# switch.net
KiCad netlist of a schematic drawn in EAGLE
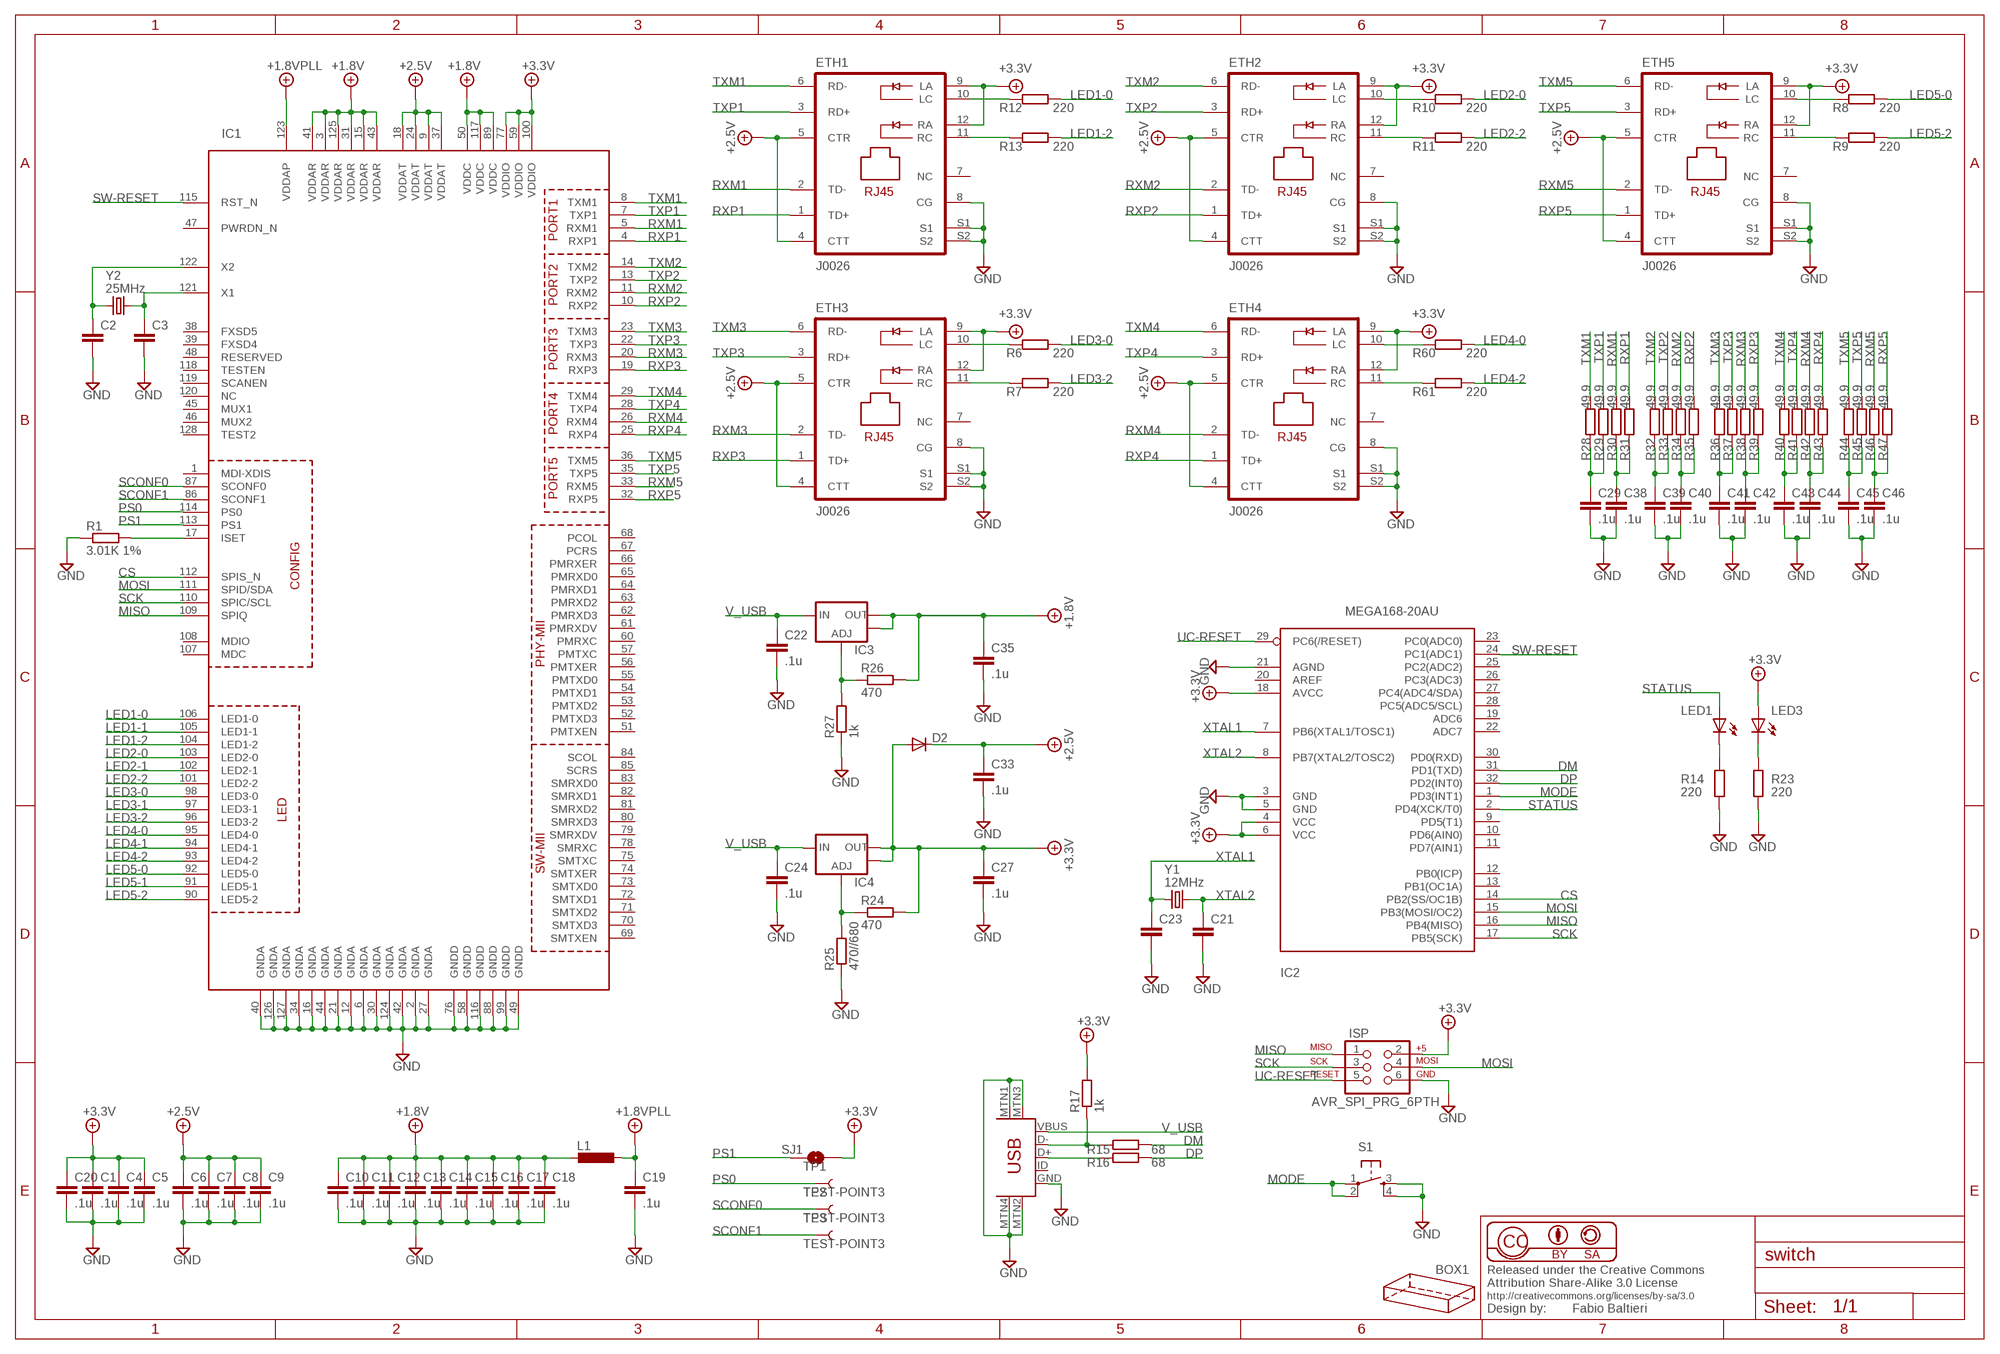
[diagram p0: schematic, sheet 1]

(export (version "E")
  (design (tool "Eeschema 10.0.6"))
  (components
    (comp (ref "BOX1")
      (value "HAMMOND-BOX-XXA")
      (footprint "eagle-import:1591XXA")
      (libsource (lib "eagle-import") (part "HAMMOND-BOX-XXA"))
    )
    (comp (ref "C1")
      (value ".1u")
      (footprint "eagle-import:C0805")
      (libsource (lib "eagle-import") (part "C-EUC0805"))
    )
    (comp (ref "C2")
      (value "C-EUC0805")
      (footprint "eagle-import:C0805")
      (libsource (lib "eagle-import") (part "C-EUC0805"))
    )
    (comp (ref "C3")
      (value "C-EUC0805")
      (footprint "eagle-import:C0805")
      (libsource (lib "eagle-import") (part "C-EUC0805"))
    )
    (comp (ref "C4")
      (value ".1u")
      (footprint "eagle-import:C0805")
      (libsource (lib "eagle-import") (part "C-EUC0805"))
    )
    (comp (ref "C5")
      (value ".1u")
      (footprint "eagle-import:C0805")
      (libsource (lib "eagle-import") (part "C-EUC0805"))
    )
    (comp (ref "C6")
      (value ".1u")
      (footprint "eagle-import:C0805")
      (libsource (lib "eagle-import") (part "C-EUC0805"))
    )
    (comp (ref "C7")
      (value ".1u")
      (footprint "eagle-import:C0805")
      (libsource (lib "eagle-import") (part "C-EUC0805"))
    )
    (comp (ref "C8")
      (value ".1u")
      (footprint "eagle-import:C0805")
      (libsource (lib "eagle-import") (part "C-EUC0805"))
    )
    (comp (ref "C9")
      (value ".1u")
      (footprint "eagle-import:C0805")
      (libsource (lib "eagle-import") (part "C-EUC0805"))
    )
    (comp (ref "C10")
      (value ".1u")
      (footprint "eagle-import:C0805")
      (libsource (lib "eagle-import") (part "C-EUC0805"))
    )
    (comp (ref "C11")
      (value ".1u")
      (footprint "eagle-import:C0805")
      (libsource (lib "eagle-import") (part "C-EUC0805"))
    )
    (comp (ref "C12")
      (value ".1u")
      (footprint "eagle-import:C0805")
      (libsource (lib "eagle-import") (part "C-EUC0805"))
    )
    (comp (ref "C13")
      (value ".1u")
      (footprint "eagle-import:C0805")
      (libsource (lib "eagle-import") (part "C-EUC0805"))
    )
    (comp (ref "C14")
      (value ".1u")
      (footprint "eagle-import:C0805")
      (libsource (lib "eagle-import") (part "C-EUC0805"))
    )
    (comp (ref "C15")
      (value ".1u")
      (footprint "eagle-import:C0805")
      (libsource (lib "eagle-import") (part "C-EUC0805"))
    )
    (comp (ref "C16")
      (value ".1u")
      (footprint "eagle-import:C0805")
      (libsource (lib "eagle-import") (part "C-EUC0805"))
    )
    (comp (ref "C17")
      (value ".1u")
      (footprint "eagle-import:C0805")
      (libsource (lib "eagle-import") (part "C-EUC0805"))
    )
    (comp (ref "C18")
      (value ".1u")
      (footprint "eagle-import:C0805")
      (libsource (lib "eagle-import") (part "C-EUC0805"))
    )
    (comp (ref "C19")
      (value ".1u")
      (footprint "eagle-import:C0805")
      (libsource (lib "eagle-import") (part "C-EUC0805"))
    )
    (comp (ref "C20")
      (value ".1u")
      (footprint "eagle-import:C0805")
      (libsource (lib "eagle-import") (part "C-EUC0805"))
    )
    (comp (ref "C21")
      (value "C-EUC0805")
      (footprint "eagle-import:C0805")
      (libsource (lib "eagle-import") (part "C-EUC0805"))
    )
    (comp (ref "C22")
      (value ".1u")
      (footprint "eagle-import:C0805")
      (libsource (lib "eagle-import") (part "C-EUC0805"))
    )
    (comp (ref "C23")
      (value "C-EUC0805")
      (footprint "eagle-import:C0805")
      (libsource (lib "eagle-import") (part "C-EUC0805"))
    )
    (comp (ref "C24")
      (value ".1u")
      (footprint "eagle-import:C0805")
      (libsource (lib "eagle-import") (part "C-EUC0805"))
    )
    (comp (ref "C27")
      (value ".1u")
      (footprint "eagle-import:C0805")
      (libsource (lib "eagle-import") (part "C-EUC0805"))
    )
    (comp (ref "C29")
      (value ".1u")
      (footprint "eagle-import:C0805")
      (libsource (lib "eagle-import") (part "C-EUC0805"))
    )
    (comp (ref "C33")
      (value ".1u")
      (footprint "eagle-import:C0805")
      (libsource (lib "eagle-import") (part "C-EUC0805"))
    )
    (comp (ref "C35")
      (value ".1u")
      (footprint "eagle-import:C0805")
      (libsource (lib "eagle-import") (part "C-EUC0805"))
    )
    (comp (ref "C38")
      (value ".1u")
      (footprint "eagle-import:C0805")
      (libsource (lib "eagle-import") (part "C-EUC0805"))
    )
    (comp (ref "C39")
      (value ".1u")
      (footprint "eagle-import:C0805")
      (libsource (lib "eagle-import") (part "C-EUC0805"))
    )
    (comp (ref "C40")
      (value ".1u")
      (footprint "eagle-import:C0805")
      (libsource (lib "eagle-import") (part "C-EUC0805"))
    )
    (comp (ref "C41")
      (value ".1u")
      (footprint "eagle-import:C0805")
      (libsource (lib "eagle-import") (part "C-EUC0805"))
    )
    (comp (ref "C42")
      (value ".1u")
      (footprint "eagle-import:C0805")
      (libsource (lib "eagle-import") (part "C-EUC0805"))
    )
    (comp (ref "C43")
      (value ".1u")
      (footprint "eagle-import:C0805")
      (libsource (lib "eagle-import") (part "C-EUC0805"))
    )
    (comp (ref "C44")
      (value ".1u")
      (footprint "eagle-import:C0805")
      (libsource (lib "eagle-import") (part "C-EUC0805"))
    )
    (comp (ref "C45")
      (value ".1u")
      (footprint "eagle-import:C0805")
      (libsource (lib "eagle-import") (part "C-EUC0805"))
    )
    (comp (ref "C46")
      (value ".1u")
      (footprint "eagle-import:C0805")
      (libsource (lib "eagle-import") (part "C-EUC0805"))
    )
    (comp (ref "D2")
      (value "DIODE-SMB")
      (footprint "eagle-import:SMB")
      (libsource (lib "eagle-import") (part "DIODE-SMB"))
    )
    (comp (ref "ETH1")
      (value "J0026")
      (footprint "eagle-import:PJ-J0")
      (libsource (lib "eagle-import") (part "J0026"))
    )
    (comp (ref "ETH2")
      (value "J0026")
      (footprint "eagle-import:PJ-J0")
      (libsource (lib "eagle-import") (part "J0026"))
    )
    (comp (ref "ETH3")
      (value "J0026")
      (footprint "eagle-import:PJ-J0")
      (libsource (lib "eagle-import") (part "J0026"))
    )
    (comp (ref "ETH4")
      (value "J0026")
      (footprint "eagle-import:PJ-J0")
      (libsource (lib "eagle-import") (part "J0026"))
    )
    (comp (ref "ETH5")
      (value "J0026")
      (footprint "eagle-import:PJ-J0")
      (libsource (lib "eagle-import") (part "J0026"))
    )
    (comp (ref "IC1")
      (value "KS8995MA")
      (footprint "eagle-import:PQFP128L")
      (libsource (lib "eagle-import") (part "KS8995MA"))
    )
    (comp (ref "IC2")
      (value "MEGA168-20AU")
      (footprint "eagle-import:MLF32")
      (libsource (lib "eagle-import") (part "MEGA8-MI"))
    )
    (comp (ref "IC3")
      (value "V_REG_LM1117SOT223")
      (footprint "eagle-import:SOT223")
      (libsource (lib "eagle-import") (part "V_REG_LM1117SOT223"))
    )
    (comp (ref "IC4")
      (value "V_REG_LM1117SOT223")
      (footprint "eagle-import:SOT223")
      (libsource (lib "eagle-import") (part "V_REG_LM1117SOT223"))
    )
    (comp (ref "ISP")
      (value "AVR_SPI_PRG_6PTH")
      (footprint "eagle-import:2X3")
      (libsource (lib "eagle-import") (part "AVR_SPI_PRG_6PTH"))
    )
    (comp (ref "L1")
      (value "L-EUL2012C")
      (footprint "eagle-import:L2012C")
      (libsource (lib "eagle-import") (part "L-EUL2012C"))
    )
    (comp (ref "LED1")
      (value "LEDCHIPLED_0603")
      (footprint "eagle-import:CHIPLED_0603")
      (libsource (lib "eagle-import") (part "LEDCHIPLED_0603"))
    )
    (comp (ref "LED3")
      (value "LEDCHIPLED_0603")
      (footprint "eagle-import:CHIPLED_0603")
      (libsource (lib "eagle-import") (part "LEDCHIPLED_0603"))
    )
    (comp (ref "R1")
      (value "3.01K 1%")
      (footprint "eagle-import:R0603")
      (libsource (lib "eagle-import") (part "R-EU_R0603"))
    )
    (comp (ref "R6")
      (value "220")
      (footprint "eagle-import:R0603")
      (libsource (lib "eagle-import") (part "R-EU_R0603"))
    )
    (comp (ref "R7")
      (value "220")
      (footprint "eagle-import:R0603")
      (libsource (lib "eagle-import") (part "R-EU_R0603"))
    )
    (comp (ref "R8")
      (value "220")
      (footprint "eagle-import:R0603")
      (libsource (lib "eagle-import") (part "R-EU_R0603"))
    )
    (comp (ref "R9")
      (value "220")
      (footprint "eagle-import:R0603")
      (libsource (lib "eagle-import") (part "R-EU_R0603"))
    )
    (comp (ref "R10")
      (value "220")
      (footprint "eagle-import:R0603")
      (libsource (lib "eagle-import") (part "R-EU_R0603"))
    )
    (comp (ref "R11")
      (value "220")
      (footprint "eagle-import:R0603")
      (libsource (lib "eagle-import") (part "R-EU_R0603"))
    )
    (comp (ref "R12")
      (value "220")
      (footprint "eagle-import:R0603")
      (libsource (lib "eagle-import") (part "R-EU_R0603"))
    )
    (comp (ref "R13")
      (value "220")
      (footprint "eagle-import:R0603")
      (libsource (lib "eagle-import") (part "R-EU_R0603"))
    )
    (comp (ref "R14")
      (value "220")
      (footprint "eagle-import:R0603")
      (libsource (lib "eagle-import") (part "R-EU_R0603"))
    )
    (comp (ref "R15")
      (value "68")
      (footprint "eagle-import:R0603")
      (libsource (lib "eagle-import") (part "R-EU_R0603"))
    )
    (comp (ref "R16")
      (value "68")
      (footprint "eagle-import:R0603")
      (libsource (lib "eagle-import") (part "R-EU_R0603"))
    )
    (comp (ref "R17")
      (value "1k")
      (footprint "eagle-import:R0603")
      (libsource (lib "eagle-import") (part "R-EU_R0603"))
    )
    (comp (ref "R23")
      (value "220")
      (footprint "eagle-import:R0603")
      (libsource (lib "eagle-import") (part "R-EU_R0603"))
    )
    (comp (ref "R24")
      (value "470")
      (footprint "eagle-import:R0603")
      (libsource (lib "eagle-import") (part "R-EU_R0603"))
    )
    (comp (ref "R25")
      (value "470//680")
      (footprint "eagle-import:R0603")
      (libsource (lib "eagle-import") (part "R-EU_R0603"))
    )
    (comp (ref "R26")
      (value "470")
      (footprint "eagle-import:R0603")
      (libsource (lib "eagle-import") (part "R-EU_R0603"))
    )
    (comp (ref "R27")
      (value "1k")
      (footprint "eagle-import:R0603")
      (libsource (lib "eagle-import") (part "R-EU_R0603"))
    )
    (comp (ref "R28")
      (value "49.9")
      (footprint "eagle-import:R0603")
      (libsource (lib "eagle-import") (part "R-EU_R0603"))
    )
    (comp (ref "R29")
      (value "49.9")
      (footprint "eagle-import:R0603")
      (libsource (lib "eagle-import") (part "R-EU_R0603"))
    )
    (comp (ref "R30")
      (value "49.9")
      (footprint "eagle-import:R0603")
      (libsource (lib "eagle-import") (part "R-EU_R0603"))
    )
    (comp (ref "R31")
      (value "49.9")
      (footprint "eagle-import:R0603")
      (libsource (lib "eagle-import") (part "R-EU_R0603"))
    )
    (comp (ref "R32")
      (value "49.9")
      (footprint "eagle-import:R0603")
      (libsource (lib "eagle-import") (part "R-EU_R0603"))
    )
    (comp (ref "R33")
      (value "49.9")
      (footprint "eagle-import:R0603")
      (libsource (lib "eagle-import") (part "R-EU_R0603"))
    )
    (comp (ref "R34")
      (value "49.9")
      (footprint "eagle-import:R0603")
      (libsource (lib "eagle-import") (part "R-EU_R0603"))
    )
    (comp (ref "R35")
      (value "49.9")
      (footprint "eagle-import:R0603")
      (libsource (lib "eagle-import") (part "R-EU_R0603"))
    )
    (comp (ref "R36")
      (value "49.9")
      (footprint "eagle-import:R0603")
      (libsource (lib "eagle-import") (part "R-EU_R0603"))
    )
    (comp (ref "R37")
      (value "49.9")
      (footprint "eagle-import:R0603")
      (libsource (lib "eagle-import") (part "R-EU_R0603"))
    )
    (comp (ref "R38")
      (value "49.9")
      (footprint "eagle-import:R0603")
      (libsource (lib "eagle-import") (part "R-EU_R0603"))
    )
    (comp (ref "R39")
      (value "49.9")
      (footprint "eagle-import:R0603")
      (libsource (lib "eagle-import") (part "R-EU_R0603"))
    )
    (comp (ref "R40")
      (value "49.9")
      (footprint "eagle-import:R0603")
      (libsource (lib "eagle-import") (part "R-EU_R0603"))
    )
    (comp (ref "R41")
      (value "49.9")
      (footprint "eagle-import:R0603")
      (libsource (lib "eagle-import") (part "R-EU_R0603"))
    )
    (comp (ref "R42")
      (value "49.9")
      (footprint "eagle-import:R0603")
      (libsource (lib "eagle-import") (part "R-EU_R0603"))
    )
    (comp (ref "R43")
      (value "49.9")
      (footprint "eagle-import:R0603")
      (libsource (lib "eagle-import") (part "R-EU_R0603"))
    )
    (comp (ref "R44")
      (value "49.9")
      (footprint "eagle-import:R0603")
      (libsource (lib "eagle-import") (part "R-EU_R0603"))
    )
    (comp (ref "R45")
      (value "49.9")
      (footprint "eagle-import:R0603")
      (libsource (lib "eagle-import") (part "R-EU_R0603"))
    )
    (comp (ref "R46")
      (value "49.9")
      (footprint "eagle-import:R0603")
      (libsource (lib "eagle-import") (part "R-EU_R0603"))
    )
    (comp (ref "R47")
      (value "49.9")
      (footprint "eagle-import:R0603")
      (libsource (lib "eagle-import") (part "R-EU_R0603"))
    )
    (comp (ref "R60")
      (value "220")
      (footprint "eagle-import:R0603")
      (libsource (lib "eagle-import") (part "R-EU_R0603"))
    )
    (comp (ref "R61")
      (value "220")
      (footprint "eagle-import:R0603")
      (libsource (lib "eagle-import") (part "R-EU_R0603"))
    )
    (comp (ref "S1")
      (value "TAC_SWITCHSMD")
      (footprint "eagle-import:TACTILE_SWITCH_SMD")
      (libsource (lib "eagle-import") (part "TAC_SWITCHSMD"))
    )
    (comp (ref "SJ1")
      (value "SOLDERJUMPERTRACE")
      (footprint "eagle-import:SJ_2S-TRACE")
      (libsource (lib "eagle-import") (part "SOLDERJUMPERTRACE"))
    )
    (comp (ref "TP1")
      (value "TEST-POINT3")
      (footprint "eagle-import:PAD.03X.03")
      (libsource (lib "eagle-import") (part "TEST-POINT3"))
    )
    (comp (ref "TP2")
      (value "TEST-POINT3")
      (footprint "eagle-import:PAD.03X.03")
      (libsource (lib "eagle-import") (part "TEST-POINT3"))
    )
    (comp (ref "TP3")
      (value "TEST-POINT3")
      (footprint "eagle-import:PAD.03X.03")
      (libsource (lib "eagle-import") (part "TEST-POINT3"))
    )
    (comp (ref "U$1")
      (value "USB-MINIB-5PIN")
      (footprint "eagle-import:USB-MINIB")
      (libsource (lib "eagle-import") (part "USB-MINIB-5PIN"))
    )
    (comp (ref "Y1")
      (value "12MHz")
      (footprint "eagle-import:CRYSTAL-SMD-5X3")
      (libsource (lib "eagle-import") (part "CRYSTAL5X3"))
    )
    (comp (ref "Y2")
      (value "25MHz")
      (footprint "eagle-import:CRYSTAL-SMD-5X3")
      (libsource (lib "eagle-import") (part "CRYSTAL5X3"))
    )
  )
  (nets
    (net (code "1") (name "+1.8V") (class "Default")
      (node (ref "C10") (pin "1") (pinfunction "1_1") (pintype "passive"))
      (node (ref "C11") (pin "1") (pinfunction "1_1") (pintype "passive"))
      (node (ref "C12") (pin "1") (pinfunction "1_1") (pintype "passive"))
      (node (ref "C13") (pin "1") (pinfunction "1_1") (pintype "passive"))
      (node (ref "C14") (pin "1") (pinfunction "1_1") (pintype "passive"))
      (node (ref "C15") (pin "1") (pinfunction "1_1") (pintype "passive"))
      (node (ref "C16") (pin "1") (pinfunction "1_1") (pintype "passive"))
      (node (ref "C17") (pin "1") (pinfunction "1_1") (pintype "passive"))
      (node (ref "C18") (pin "1") (pinfunction "1_1") (pintype "passive"))
      (node (ref "C35") (pin "1") (pinfunction "1_1") (pintype "passive"))
      (node (ref "IC1") (pin "117") (pinfunction "VDDC_117") (pintype "bidirectional"))
      (node (ref "IC1") (pin "125") (pinfunction "VDDAR_125") (pintype "bidirectional"))
      (node (ref "IC1") (pin "15") (pinfunction "VDDAR_15") (pintype "bidirectional"))
      (node (ref "IC1") (pin "3") (pinfunction "VDDAR_3") (pintype "bidirectional"))
      (node (ref "IC1") (pin "31") (pinfunction "VDDAR_31") (pintype "bidirectional"))
      (node (ref "IC1") (pin "41") (pinfunction "VDDAR_41") (pintype "bidirectional"))
      (node (ref "IC1") (pin "43") (pinfunction "VDDAR_43") (pintype "bidirectional"))
      (node (ref "IC1") (pin "50") (pinfunction "VDDC_50") (pintype "bidirectional"))
      (node (ref "IC1") (pin "89") (pinfunction "VDDC_89") (pintype "bidirectional"))
      (node (ref "IC3") (pin "2") (pinfunction "OUT_2") (pintype "output"))
      (node (ref "IC3") (pin "4") (pinfunction "OUT_4") (pintype "output"))
      (node (ref "L1") (pin "2") (pinfunction "2_2") (pintype "passive"))
      (node (ref "R26") (pin "2") (pinfunction "2_2") (pintype "passive"))
    )
    (net (code "2") (name "+1.8VPLL") (class "Default")
      (node (ref "C19") (pin "1") (pinfunction "1_1") (pintype "passive"))
      (node (ref "IC1") (pin "123") (pinfunction "VDDAP_123") (pintype "bidirectional"))
      (node (ref "L1") (pin "1") (pinfunction "1_1") (pintype "passive"))
    )
    (net (code "3") (name "+2.5V") (class "Default")
      (node (ref "C33") (pin "1") (pinfunction "1_1") (pintype "passive"))
      (node (ref "C6") (pin "1") (pinfunction "1_1") (pintype "passive"))
      (node (ref "C7") (pin "1") (pinfunction "1_1") (pintype "passive"))
      (node (ref "C8") (pin "1") (pinfunction "1_1") (pintype "passive"))
      (node (ref "C9") (pin "1") (pinfunction "1_1") (pintype "passive"))
      (node (ref "D2") (pin "C") (pinfunction "C_C") (pintype "passive"))
      (node (ref "ETH1") (pin "4") (pinfunction "CTT_4") (pintype "bidirectional"))
      (node (ref "ETH1") (pin "5") (pinfunction "CTR_5") (pintype "bidirectional"))
      (node (ref "ETH2") (pin "4") (pinfunction "CTT_4") (pintype "bidirectional"))
      (node (ref "ETH2") (pin "5") (pinfunction "CTR_5") (pintype "bidirectional"))
      (node (ref "ETH3") (pin "4") (pinfunction "CTT_4") (pintype "bidirectional"))
      (node (ref "ETH3") (pin "5") (pinfunction "CTR_5") (pintype "bidirectional"))
      (node (ref "ETH4") (pin "4") (pinfunction "CTT_4") (pintype "bidirectional"))
      (node (ref "ETH4") (pin "5") (pinfunction "CTR_5") (pintype "bidirectional"))
      (node (ref "ETH5") (pin "4") (pinfunction "CTT_4") (pintype "bidirectional"))
      (node (ref "ETH5") (pin "5") (pinfunction "CTR_5") (pintype "bidirectional"))
      (node (ref "IC1") (pin "18") (pinfunction "VDDAT_18") (pintype "bidirectional"))
      (node (ref "IC1") (pin "24") (pinfunction "VDDAT_24") (pintype "bidirectional"))
      (node (ref "IC1") (pin "37") (pinfunction "VDDAT_37") (pintype "bidirectional"))
      (node (ref "IC1") (pin "9") (pinfunction "VDDAT_9") (pintype "bidirectional"))
    )
    (net (code "4") (name "+3.3V") (class "Default")
      (node (ref "C1") (pin "1") (pinfunction "1_1") (pintype "passive"))
      (node (ref "C20") (pin "1") (pinfunction "1_1") (pintype "passive"))
      (node (ref "C27") (pin "1") (pinfunction "1_1") (pintype "passive"))
      (node (ref "C4") (pin "1") (pinfunction "1_1") (pintype "passive"))
      (node (ref "C5") (pin "1") (pinfunction "1_1") (pintype "passive"))
      (node (ref "D2") (pin "A") (pinfunction "A_A") (pintype "passive"))
      (node (ref "ETH1") (pin "12") (pinfunction "RA_12") (pintype "passive"))
      (node (ref "ETH1") (pin "9") (pinfunction "LA_9") (pintype "passive"))
      (node (ref "ETH2") (pin "12") (pinfunction "RA_12") (pintype "passive"))
      (node (ref "ETH2") (pin "9") (pinfunction "LA_9") (pintype "passive"))
      (node (ref "ETH3") (pin "12") (pinfunction "RA_12") (pintype "passive"))
      (node (ref "ETH3") (pin "9") (pinfunction "LA_9") (pintype "passive"))
      (node (ref "ETH4") (pin "12") (pinfunction "RA_12") (pintype "passive"))
      (node (ref "ETH4") (pin "9") (pinfunction "LA_9") (pintype "passive"))
      (node (ref "ETH5") (pin "12") (pinfunction "RA_12") (pintype "passive"))
      (node (ref "ETH5") (pin "9") (pinfunction "LA_9") (pintype "passive"))
      (node (ref "IC1") (pin "100") (pinfunction "VDDIO_100") (pintype "bidirectional"))
      (node (ref "IC1") (pin "59") (pinfunction "VDDIO_59") (pintype "bidirectional"))
      (node (ref "IC1") (pin "77") (pinfunction "VDDIO_77") (pintype "bidirectional"))
      (node (ref "IC2") (pin "18") (pinfunction "AVCC_18") (pintype "power_in"))
      (node (ref "IC2") (pin "4") (pinfunction "VCC_4") (pintype "power_in"))
      (node (ref "IC2") (pin "6") (pinfunction "VCC_6") (pintype "power_in"))
      (node (ref "IC4") (pin "2") (pinfunction "OUT_2") (pintype "output"))
      (node (ref "IC4") (pin "4") (pinfunction "OUT_4") (pintype "output"))
      (node (ref "ISP") (pin "2") (pinfunction "2_2") (pintype "passive"))
      (node (ref "LED3") (pin "A") (pinfunction "A_A") (pintype "passive"))
      (node (ref "R17") (pin "2") (pinfunction "2_2") (pintype "passive"))
      (node (ref "R24") (pin "2") (pinfunction "2_2") (pintype "passive"))
      (node (ref "SJ1") (pin "2") (pinfunction "2_2") (pintype "passive"))
    )
    (net (code "5") (name "/CS") (class "Default")
      (node (ref "IC1") (pin "112") (pinfunction "SPIS_N_112") (pintype "bidirectional"))
      (node (ref "IC2") (pin "14") (pinfunction "PB2(SS/OC1B)_14") (pintype "bidirectional"))
    )
    (net (code "6") (name "/DM") (class "Default")
      (node (ref "IC2") (pin "31") (pinfunction "PD1(TXD)_31") (pintype "bidirectional"))
      (node (ref "R15") (pin "1") (pinfunction "1_1") (pintype "passive"))
    )
    (net (code "7") (name "/DP") (class "Default")
      (node (ref "IC2") (pin "32") (pinfunction "PD2(INT0)_32") (pintype "bidirectional"))
      (node (ref "R16") (pin "1") (pinfunction "1_1") (pintype "passive"))
    )
    (net (code "8") (name "/LED1-0") (class "Default")
      (node (ref "IC1") (pin "106") (pinfunction "LED1-0_106") (pintype "bidirectional"))
      (node (ref "R12") (pin "1") (pinfunction "1_1") (pintype "passive"))
    )
    (net (code "9") (name "/LED1-1") (class "Default")
      (node (ref "IC1") (pin "105") (pinfunction "LED1-1_105") (pintype "bidirectional"))
    )
    (net (code "10") (name "/LED1-2") (class "Default")
      (node (ref "IC1") (pin "104") (pinfunction "LED1-2_104") (pintype "bidirectional"))
      (node (ref "R13") (pin "1") (pinfunction "1_1") (pintype "passive"))
    )
    (net (code "11") (name "/LED2-0") (class "Default")
      (node (ref "IC1") (pin "103") (pinfunction "LED2-0_103") (pintype "bidirectional"))
      (node (ref "R10") (pin "1") (pinfunction "1_1") (pintype "passive"))
    )
    (net (code "12") (name "/LED2-1") (class "Default")
      (node (ref "IC1") (pin "102") (pinfunction "LED2-1_102") (pintype "bidirectional"))
    )
    (net (code "13") (name "/LED2-2") (class "Default")
      (node (ref "IC1") (pin "101") (pinfunction "LED2-2_101") (pintype "bidirectional"))
      (node (ref "R11") (pin "1") (pinfunction "1_1") (pintype "passive"))
    )
    (net (code "14") (name "/LED3-0") (class "Default")
      (node (ref "IC1") (pin "98") (pinfunction "LED3-0_98") (pintype "bidirectional"))
      (node (ref "R6") (pin "1") (pinfunction "1_1") (pintype "passive"))
    )
    (net (code "15") (name "/LED3-1") (class "Default")
      (node (ref "IC1") (pin "97") (pinfunction "LED3-1_97") (pintype "bidirectional"))
    )
    (net (code "16") (name "/LED3-2") (class "Default")
      (node (ref "IC1") (pin "96") (pinfunction "LED3-2_96") (pintype "bidirectional"))
      (node (ref "R7") (pin "1") (pinfunction "1_1") (pintype "passive"))
    )
    (net (code "17") (name "/LED4-0") (class "Default")
      (node (ref "IC1") (pin "95") (pinfunction "LED4-0_95") (pintype "bidirectional"))
      (node (ref "R60") (pin "1") (pinfunction "1_1") (pintype "passive"))
    )
    (net (code "18") (name "/LED4-1") (class "Default")
      (node (ref "IC1") (pin "94") (pinfunction "LED4-1_94") (pintype "bidirectional"))
    )
    (net (code "19") (name "/LED4-2") (class "Default")
      (node (ref "IC1") (pin "93") (pinfunction "LED4-2_93") (pintype "bidirectional"))
      (node (ref "R61") (pin "1") (pinfunction "1_1") (pintype "passive"))
    )
    (net (code "20") (name "/LED5-0") (class "Default")
      (node (ref "IC1") (pin "92") (pinfunction "LED5-0_92") (pintype "bidirectional"))
      (node (ref "R8") (pin "1") (pinfunction "1_1") (pintype "passive"))
    )
    (net (code "21") (name "/LED5-1") (class "Default")
      (node (ref "IC1") (pin "91") (pinfunction "LED5-1_91") (pintype "bidirectional"))
    )
    (net (code "22") (name "/LED5-2") (class "Default")
      (node (ref "IC1") (pin "90") (pinfunction "LED5-2_90") (pintype "bidirectional"))
      (node (ref "R9") (pin "1") (pinfunction "1_1") (pintype "passive"))
    )
    (net (code "23") (name "/MISO") (class "Default")
      (node (ref "IC1") (pin "109") (pinfunction "SPIQ_109") (pintype "bidirectional"))
      (node (ref "IC2") (pin "16") (pinfunction "PB4(MISO)_16") (pintype "bidirectional"))
      (node (ref "ISP") (pin "1") (pinfunction "1_1") (pintype "passive"))
    )
    (net (code "24") (name "/MODE") (class "Default")
      (node (ref "IC2") (pin "1") (pinfunction "PD3(INT1)_1") (pintype "bidirectional"))
      (node (ref "S1") (pin "1") (pinfunction "1_1") (pintype "passive"))
      (node (ref "S1") (pin "2") (pinfunction "2_2") (pintype "passive"))
    )
    (net (code "25") (name "/MOSI") (class "Default")
      (node (ref "IC1") (pin "111") (pinfunction "SPID/SDA_111") (pintype "bidirectional"))
      (node (ref "IC2") (pin "15") (pinfunction "PB3(MOSI/OC2)_15") (pintype "bidirectional"))
      (node (ref "ISP") (pin "4") (pinfunction "4_4") (pintype "passive"))
    )
    (net (code "26") (name "/PS0") (class "Default")
      (node (ref "IC1") (pin "114") (pinfunction "PS0_114") (pintype "bidirectional"))
      (node (ref "TP1") (pin "P$1") (pinfunction "1_P$1") (pintype "bidirectional"))
    )
    (net (code "27") (name "/PS1") (class "Default")
      (node (ref "IC1") (pin "113") (pinfunction "PS1_113") (pintype "bidirectional"))
      (node (ref "SJ1") (pin "1") (pinfunction "1_1") (pintype "passive"))
    )
    (net (code "28") (name "/RXM1") (class "Default")
      (node (ref "ETH1") (pin "2") (pinfunction "TD-_2") (pintype "bidirectional"))
      (node (ref "IC1") (pin "5") (pinfunction "RXM1_5") (pintype "bidirectional"))
      (node (ref "R30") (pin "2") (pinfunction "2_2") (pintype "passive"))
    )
    (net (code "29") (name "/RXM2") (class "Default")
      (node (ref "ETH2") (pin "2") (pinfunction "TD-_2") (pintype "bidirectional"))
      (node (ref "IC1") (pin "11") (pinfunction "RXM2_11") (pintype "bidirectional"))
      (node (ref "R34") (pin "2") (pinfunction "2_2") (pintype "passive"))
    )
    (net (code "30") (name "/RXM3") (class "Default")
      (node (ref "ETH3") (pin "2") (pinfunction "TD-_2") (pintype "bidirectional"))
      (node (ref "IC1") (pin "20") (pinfunction "RXM3_20") (pintype "bidirectional"))
      (node (ref "R38") (pin "2") (pinfunction "2_2") (pintype "passive"))
    )
    (net (code "31") (name "/RXM4") (class "Default")
      (node (ref "ETH4") (pin "2") (pinfunction "TD-_2") (pintype "bidirectional"))
      (node (ref "IC1") (pin "26") (pinfunction "RXM4_26") (pintype "bidirectional"))
      (node (ref "R42") (pin "2") (pinfunction "2_2") (pintype "passive"))
    )
    (net (code "32") (name "/RXM5") (class "Default")
      (node (ref "ETH5") (pin "2") (pinfunction "TD-_2") (pintype "bidirectional"))
      (node (ref "IC1") (pin "33") (pinfunction "RXM5_33") (pintype "bidirectional"))
      (node (ref "R46") (pin "2") (pinfunction "2_2") (pintype "passive"))
    )
    (net (code "33") (name "/RXP1") (class "Default")
      (node (ref "ETH1") (pin "1") (pinfunction "TD+_1") (pintype "bidirectional"))
      (node (ref "IC1") (pin "4") (pinfunction "RXP1_4") (pintype "bidirectional"))
      (node (ref "R31") (pin "2") (pinfunction "2_2") (pintype "passive"))
    )
    (net (code "34") (name "/RXP2") (class "Default")
      (node (ref "ETH2") (pin "1") (pinfunction "TD+_1") (pintype "bidirectional"))
      (node (ref "IC1") (pin "10") (pinfunction "RXP2_10") (pintype "bidirectional"))
      (node (ref "R35") (pin "2") (pinfunction "2_2") (pintype "passive"))
    )
    (net (code "35") (name "/RXP3") (class "Default")
      (node (ref "ETH3") (pin "1") (pinfunction "TD+_1") (pintype "bidirectional"))
      (node (ref "IC1") (pin "19") (pinfunction "RXP3_19") (pintype "bidirectional"))
      (node (ref "R39") (pin "2") (pinfunction "2_2") (pintype "passive"))
    )
    (net (code "36") (name "/RXP4") (class "Default")
      (node (ref "ETH4") (pin "1") (pinfunction "TD+_1") (pintype "bidirectional"))
      (node (ref "IC1") (pin "25") (pinfunction "RXP4_25") (pintype "bidirectional"))
      (node (ref "R43") (pin "2") (pinfunction "2_2") (pintype "passive"))
    )
    (net (code "37") (name "/RXP5") (class "Default")
      (node (ref "ETH5") (pin "1") (pinfunction "TD+_1") (pintype "bidirectional"))
      (node (ref "IC1") (pin "32") (pinfunction "RXP5_32") (pintype "bidirectional"))
      (node (ref "R47") (pin "2") (pinfunction "2_2") (pintype "passive"))
    )
    (net (code "38") (name "/SCK") (class "Default")
      (node (ref "IC1") (pin "110") (pinfunction "SPIC/SCL_110") (pintype "bidirectional"))
      (node (ref "IC2") (pin "17") (pinfunction "PB5(SCK)_17") (pintype "bidirectional"))
      (node (ref "ISP") (pin "3") (pinfunction "3_3") (pintype "passive"))
    )
    (net (code "39") (name "/SCONF0") (class "Default")
      (node (ref "IC1") (pin "87") (pinfunction "SCONF0_87") (pintype "bidirectional"))
      (node (ref "TP2") (pin "P$1") (pinfunction "1_P$1") (pintype "bidirectional"))
    )
    (net (code "40") (name "/SCONF1") (class "Default")
      (node (ref "IC1") (pin "86") (pinfunction "SCONF1_86") (pintype "bidirectional"))
      (node (ref "TP3") (pin "P$1") (pinfunction "1_P$1") (pintype "bidirectional"))
    )
    (net (code "41") (name "/STATUS") (class "Default")
      (node (ref "IC2") (pin "2") (pinfunction "PD4(XCK/T0)_2") (pintype "bidirectional"))
      (node (ref "LED1") (pin "A") (pinfunction "A_A") (pintype "passive"))
    )
    (net (code "42") (name "/SW-RESET") (class "Default")
      (node (ref "IC1") (pin "115") (pinfunction "RST_N_115") (pintype "bidirectional"))
      (node (ref "IC2") (pin "24") (pinfunction "PC1(ADC1)_24") (pintype "bidirectional"))
    )
    (net (code "43") (name "/TXM1") (class "Default")
      (node (ref "ETH1") (pin "6") (pinfunction "RD-_6") (pintype "bidirectional"))
      (node (ref "IC1") (pin "8") (pinfunction "TXM1_8") (pintype "bidirectional"))
      (node (ref "R28") (pin "2") (pinfunction "2_2") (pintype "passive"))
    )
    (net (code "44") (name "/TXM2") (class "Default")
      (node (ref "ETH2") (pin "6") (pinfunction "RD-_6") (pintype "bidirectional"))
      (node (ref "IC1") (pin "14") (pinfunction "TXM2_14") (pintype "bidirectional"))
      (node (ref "R32") (pin "2") (pinfunction "2_2") (pintype "passive"))
    )
    (net (code "45") (name "/TXM3") (class "Default")
      (node (ref "ETH3") (pin "6") (pinfunction "RD-_6") (pintype "bidirectional"))
      (node (ref "IC1") (pin "23") (pinfunction "TXM3_23") (pintype "bidirectional"))
      (node (ref "R36") (pin "2") (pinfunction "2_2") (pintype "passive"))
    )
    (net (code "46") (name "/TXM4") (class "Default")
      (node (ref "ETH4") (pin "6") (pinfunction "RD-_6") (pintype "bidirectional"))
      (node (ref "IC1") (pin "29") (pinfunction "TXM4_29") (pintype "bidirectional"))
      (node (ref "R40") (pin "2") (pinfunction "2_2") (pintype "passive"))
    )
    (net (code "47") (name "/TXM5") (class "Default")
      (node (ref "ETH5") (pin "6") (pinfunction "RD-_6") (pintype "bidirectional"))
      (node (ref "IC1") (pin "36") (pinfunction "TXM5_36") (pintype "bidirectional"))
      (node (ref "R44") (pin "2") (pinfunction "2_2") (pintype "passive"))
    )
    (net (code "48") (name "/TXP1") (class "Default")
      (node (ref "ETH1") (pin "3") (pinfunction "RD+_3") (pintype "bidirectional"))
      (node (ref "IC1") (pin "7") (pinfunction "TXP1_7") (pintype "bidirectional"))
      (node (ref "R29") (pin "2") (pinfunction "2_2") (pintype "passive"))
    )
    (net (code "49") (name "/TXP2") (class "Default")
      (node (ref "ETH2") (pin "3") (pinfunction "RD+_3") (pintype "bidirectional"))
      (node (ref "IC1") (pin "13") (pinfunction "TXP2_13") (pintype "bidirectional"))
      (node (ref "R33") (pin "2") (pinfunction "2_2") (pintype "passive"))
    )
    (net (code "50") (name "/TXP3") (class "Default")
      (node (ref "ETH3") (pin "3") (pinfunction "RD+_3") (pintype "bidirectional"))
      (node (ref "IC1") (pin "22") (pinfunction "TXP3_22") (pintype "bidirectional"))
      (node (ref "R37") (pin "2") (pinfunction "2_2") (pintype "passive"))
    )
    (net (code "51") (name "/TXP4") (class "Default")
      (node (ref "ETH4") (pin "3") (pinfunction "RD+_3") (pintype "bidirectional"))
      (node (ref "IC1") (pin "28") (pinfunction "TXP4_28") (pintype "bidirectional"))
      (node (ref "R41") (pin "2") (pinfunction "2_2") (pintype "passive"))
    )
    (net (code "52") (name "/TXP5") (class "Default")
      (node (ref "ETH5") (pin "3") (pinfunction "RD+_3") (pintype "bidirectional"))
      (node (ref "IC1") (pin "35") (pinfunction "TXP5_35") (pintype "bidirectional"))
      (node (ref "R45") (pin "2") (pinfunction "2_2") (pintype "passive"))
    )
    (net (code "53") (name "/UC-RESET") (class "Default")
      (node (ref "IC2") (pin "29") (pinfunction "PC6(/RESET)_29") (pintype "bidirectional"))
      (node (ref "ISP") (pin "5") (pinfunction "5_5") (pintype "passive"))
    )
    (net (code "54") (name "/V_USB") (class "Default")
      (node (ref "C22") (pin "1") (pinfunction "1_1") (pintype "passive"))
      (node (ref "C24") (pin "1") (pinfunction "1_1") (pintype "passive"))
      (node (ref "IC3") (pin "3") (pinfunction "IN_3") (pintype "input"))
      (node (ref "IC4") (pin "3") (pinfunction "IN_3") (pintype "input"))
      (node (ref "U$1") (pin "VBUS") (pinfunction "VBUS_VBUS") (pintype "bidirectional"))
    )
    (net (code "55") (name "/XTAL1") (class "Default")
      (node (ref "C23") (pin "1") (pinfunction "1_1") (pintype "passive"))
      (node (ref "IC2") (pin "7") (pinfunction "PB6(XTAL1/TOSC1)_7") (pintype "bidirectional"))
      (node (ref "Y1") (pin "1") (pinfunction "1_1") (pintype "passive"))
    )
    (net (code "56") (name "/XTAL2") (class "Default")
      (node (ref "C21") (pin "1") (pinfunction "1_1") (pintype "passive"))
      (node (ref "IC2") (pin "8") (pinfunction "PB7(XTAL2/TOSC2)_8") (pintype "bidirectional"))
      (node (ref "Y1") (pin "3") (pinfunction "2_3") (pintype "passive"))
    )
    (net (code "57") (name "GND") (class "Default")
      (node (ref "C1") (pin "2") (pinfunction "2_2") (pintype "passive"))
      (node (ref "C10") (pin "2") (pinfunction "2_2") (pintype "passive"))
      (node (ref "C11") (pin "2") (pinfunction "2_2") (pintype "passive"))
      (node (ref "C12") (pin "2") (pinfunction "2_2") (pintype "passive"))
      (node (ref "C13") (pin "2") (pinfunction "2_2") (pintype "passive"))
      (node (ref "C14") (pin "2") (pinfunction "2_2") (pintype "passive"))
      (node (ref "C15") (pin "2") (pinfunction "2_2") (pintype "passive"))
      (node (ref "C16") (pin "2") (pinfunction "2_2") (pintype "passive"))
      (node (ref "C17") (pin "2") (pinfunction "2_2") (pintype "passive"))
      (node (ref "C18") (pin "2") (pinfunction "2_2") (pintype "passive"))
      (node (ref "C19") (pin "2") (pinfunction "2_2") (pintype "passive"))
      (node (ref "C2") (pin "2") (pinfunction "2_2") (pintype "passive"))
      (node (ref "C20") (pin "2") (pinfunction "2_2") (pintype "passive"))
      (node (ref "C21") (pin "2") (pinfunction "2_2") (pintype "passive"))
      (node (ref "C22") (pin "2") (pinfunction "2_2") (pintype "passive"))
      (node (ref "C23") (pin "2") (pinfunction "2_2") (pintype "passive"))
      (node (ref "C24") (pin "2") (pinfunction "2_2") (pintype "passive"))
      (node (ref "C27") (pin "2") (pinfunction "2_2") (pintype "passive"))
      (node (ref "C29") (pin "2") (pinfunction "2_2") (pintype "passive"))
      (node (ref "C3") (pin "2") (pinfunction "2_2") (pintype "passive"))
      (node (ref "C33") (pin "2") (pinfunction "2_2") (pintype "passive"))
      (node (ref "C35") (pin "2") (pinfunction "2_2") (pintype "passive"))
      (node (ref "C38") (pin "2") (pinfunction "2_2") (pintype "passive"))
      (node (ref "C39") (pin "2") (pinfunction "2_2") (pintype "passive"))
      (node (ref "C4") (pin "2") (pinfunction "2_2") (pintype "passive"))
      (node (ref "C40") (pin "2") (pinfunction "2_2") (pintype "passive"))
      (node (ref "C41") (pin "2") (pinfunction "2_2") (pintype "passive"))
      (node (ref "C42") (pin "2") (pinfunction "2_2") (pintype "passive"))
      (node (ref "C43") (pin "2") (pinfunction "2_2") (pintype "passive"))
      (node (ref "C44") (pin "2") (pinfunction "2_2") (pintype "passive"))
      (node (ref "C45") (pin "2") (pinfunction "2_2") (pintype "passive"))
      (node (ref "C46") (pin "2") (pinfunction "2_2") (pintype "passive"))
      (node (ref "C5") (pin "2") (pinfunction "2_2") (pintype "passive"))
      (node (ref "C6") (pin "2") (pinfunction "2_2") (pintype "passive"))
      (node (ref "C7") (pin "2") (pinfunction "2_2") (pintype "passive"))
      (node (ref "C8") (pin "2") (pinfunction "2_2") (pintype "passive"))
      (node (ref "C9") (pin "2") (pinfunction "2_2") (pintype "passive"))
      (node (ref "ETH1") (pin "8") (pinfunction "CG_8") (pintype "passive"))
      (node (ref "ETH1") (pin "S1") (pinfunction "S1_S1") (pintype "passive"))
      (node (ref "ETH1") (pin "S2") (pinfunction "S2_S2") (pintype "passive"))
      (node (ref "ETH2") (pin "8") (pinfunction "CG_8") (pintype "passive"))
      (node (ref "ETH2") (pin "S1") (pinfunction "S1_S1") (pintype "passive"))
      (node (ref "ETH2") (pin "S2") (pinfunction "S2_S2") (pintype "passive"))
      (node (ref "ETH3") (pin "8") (pinfunction "CG_8") (pintype "passive"))
      (node (ref "ETH3") (pin "S1") (pinfunction "S1_S1") (pintype "passive"))
      (node (ref "ETH3") (pin "S2") (pinfunction "S2_S2") (pintype "passive"))
      (node (ref "ETH4") (pin "8") (pinfunction "CG_8") (pintype "passive"))
      (node (ref "ETH4") (pin "S1") (pinfunction "S1_S1") (pintype "passive"))
      (node (ref "ETH4") (pin "S2") (pinfunction "S2_S2") (pintype "passive"))
      (node (ref "ETH5") (pin "8") (pinfunction "CG_8") (pintype "passive"))
      (node (ref "ETH5") (pin "S1") (pinfunction "S1_S1") (pintype "passive"))
      (node (ref "ETH5") (pin "S2") (pinfunction "S2_S2") (pintype "passive"))
      (node (ref "IC1") (pin "116") (pinfunction "GNDD_116") (pintype "bidirectional"))
      (node (ref "IC1") (pin "12") (pinfunction "GNDA_12") (pintype "bidirectional"))
      (node (ref "IC1") (pin "124") (pinfunction "GNDA_124") (pintype "bidirectional"))
      (node (ref "IC1") (pin "126") (pinfunction "GNDA_126") (pintype "bidirectional"))
      (node (ref "IC1") (pin "127") (pinfunction "GNDA_127") (pintype "bidirectional"))
      (node (ref "IC1") (pin "16") (pinfunction "GNDA_16") (pintype "bidirectional"))
      (node (ref "IC1") (pin "2") (pinfunction "GNDA_2") (pintype "bidirectional"))
      (node (ref "IC1") (pin "21") (pinfunction "GNDA_21") (pintype "bidirectional"))
      (node (ref "IC1") (pin "27") (pinfunction "GNDA_27") (pintype "bidirectional"))
      (node (ref "IC1") (pin "30") (pinfunction "GNDA_30") (pintype "bidirectional"))
      (node (ref "IC1") (pin "34") (pinfunction "GNDA_34") (pintype "bidirectional"))
      (node (ref "IC1") (pin "40") (pinfunction "GNDA_40") (pintype "bidirectional"))
      (node (ref "IC1") (pin "42") (pinfunction "GNDA_42") (pintype "bidirectional"))
      (node (ref "IC1") (pin "44") (pinfunction "GNDA_44") (pintype "bidirectional"))
      (node (ref "IC1") (pin "49") (pinfunction "GNDD_49") (pintype "bidirectional"))
      (node (ref "IC1") (pin "58") (pinfunction "GNDD_58") (pintype "bidirectional"))
      (node (ref "IC1") (pin "6") (pinfunction "GNDA_6") (pintype "bidirectional"))
      (node (ref "IC1") (pin "76") (pinfunction "GNDD_76") (pintype "bidirectional"))
      (node (ref "IC1") (pin "88") (pinfunction "GNDD_88") (pintype "bidirectional"))
      (node (ref "IC1") (pin "99") (pinfunction "GNDD_99") (pintype "bidirectional"))
      (node (ref "IC2") (pin "21") (pinfunction "AGND_21") (pintype "power_in"))
      (node (ref "IC2") (pin "3") (pinfunction "GND_3") (pintype "power_in"))
      (node (ref "IC2") (pin "5") (pinfunction "GND_5") (pintype "power_in"))
      (node (ref "ISP") (pin "6") (pinfunction "6_6") (pintype "passive"))
      (node (ref "R1") (pin "1") (pinfunction "1_1") (pintype "passive"))
      (node (ref "R14") (pin "1") (pinfunction "1_1") (pintype "passive"))
      (node (ref "R23") (pin "1") (pinfunction "1_1") (pintype "passive"))
      (node (ref "R25") (pin "1") (pinfunction "1_1") (pintype "passive"))
      (node (ref "R27") (pin "1") (pinfunction "1_1") (pintype "passive"))
      (node (ref "S1") (pin "3") (pinfunction "3_3") (pintype "passive"))
      (node (ref "S1") (pin "4") (pinfunction "4_4") (pintype "passive"))
      (node (ref "U$1") (pin "GND") (pinfunction "GND_GND") (pintype "bidirectional"))
      (node (ref "U$1") (pin "MTN1") (pinfunction "MTN2_MTN1") (pintype "bidirectional"))
      (node (ref "U$1") (pin "MTN2") (pinfunction "MTN3_MTN2") (pintype "bidirectional"))
      (node (ref "U$1") (pin "MTN3") (pinfunction "MTN1_MTN3") (pintype "bidirectional"))
      (node (ref "U$1") (pin "MTN4") (pinfunction "MTN4_MTN4") (pintype "bidirectional"))
    )
    (net (code "58") (name "Net-(C29-Pad1)") (class "Default")
      (node (ref "C29") (pin "1") (pinfunction "1_1") (pintype "passive"))
      (node (ref "R28") (pin "1") (pinfunction "1_1") (pintype "passive"))
      (node (ref "R29") (pin "1") (pinfunction "1_1") (pintype "passive"))
    )
    (net (code "59") (name "Net-(C38-Pad1)") (class "Default")
      (node (ref "C38") (pin "1") (pinfunction "1_1") (pintype "passive"))
      (node (ref "R30") (pin "1") (pinfunction "1_1") (pintype "passive"))
      (node (ref "R31") (pin "1") (pinfunction "1_1") (pintype "passive"))
    )
    (net (code "60") (name "Net-(C39-Pad1)") (class "Default")
      (node (ref "C39") (pin "1") (pinfunction "1_1") (pintype "passive"))
      (node (ref "R32") (pin "1") (pinfunction "1_1") (pintype "passive"))
      (node (ref "R33") (pin "1") (pinfunction "1_1") (pintype "passive"))
    )
    (net (code "61") (name "Net-(C40-Pad1)") (class "Default")
      (node (ref "C40") (pin "1") (pinfunction "1_1") (pintype "passive"))
      (node (ref "R34") (pin "1") (pinfunction "1_1") (pintype "passive"))
      (node (ref "R35") (pin "1") (pinfunction "1_1") (pintype "passive"))
    )
    (net (code "62") (name "Net-(C41-Pad1)") (class "Default")
      (node (ref "C41") (pin "1") (pinfunction "1_1") (pintype "passive"))
      (node (ref "R36") (pin "1") (pinfunction "1_1") (pintype "passive"))
      (node (ref "R37") (pin "1") (pinfunction "1_1") (pintype "passive"))
    )
    (net (code "63") (name "Net-(C42-Pad1)") (class "Default")
      (node (ref "C42") (pin "1") (pinfunction "1_1") (pintype "passive"))
      (node (ref "R38") (pin "1") (pinfunction "1_1") (pintype "passive"))
      (node (ref "R39") (pin "1") (pinfunction "1_1") (pintype "passive"))
    )
    (net (code "64") (name "Net-(C43-Pad1)") (class "Default")
      (node (ref "C43") (pin "1") (pinfunction "1_1") (pintype "passive"))
      (node (ref "R40") (pin "1") (pinfunction "1_1") (pintype "passive"))
      (node (ref "R41") (pin "1") (pinfunction "1_1") (pintype "passive"))
    )
    (net (code "65") (name "Net-(C44-Pad1)") (class "Default")
      (node (ref "C44") (pin "1") (pinfunction "1_1") (pintype "passive"))
      (node (ref "R42") (pin "1") (pinfunction "1_1") (pintype "passive"))
      (node (ref "R43") (pin "1") (pinfunction "1_1") (pintype "passive"))
    )
    (net (code "66") (name "Net-(C45-Pad1)") (class "Default")
      (node (ref "C45") (pin "1") (pinfunction "1_1") (pintype "passive"))
      (node (ref "R44") (pin "1") (pinfunction "1_1") (pintype "passive"))
      (node (ref "R45") (pin "1") (pinfunction "1_1") (pintype "passive"))
    )
    (net (code "67") (name "Net-(C46-Pad1)") (class "Default")
      (node (ref "C46") (pin "1") (pinfunction "1_1") (pintype "passive"))
      (node (ref "R46") (pin "1") (pinfunction "1_1") (pintype "passive"))
      (node (ref "R47") (pin "1") (pinfunction "1_1") (pintype "passive"))
    )
    (net (code "68") (name "Net-(ETH1-LC)") (class "Default")
      (node (ref "ETH1") (pin "10") (pinfunction "LC_10") (pintype "passive"))
      (node (ref "R12") (pin "2") (pinfunction "2_2") (pintype "passive"))
    )
    (net (code "69") (name "Net-(ETH1-RC)") (class "Default")
      (node (ref "ETH1") (pin "11") (pinfunction "RC_11") (pintype "passive"))
      (node (ref "R13") (pin "2") (pinfunction "2_2") (pintype "passive"))
    )
    (net (code "70") (name "Net-(ETH2-LC)") (class "Default")
      (node (ref "ETH2") (pin "10") (pinfunction "LC_10") (pintype "passive"))
      (node (ref "R10") (pin "2") (pinfunction "2_2") (pintype "passive"))
    )
    (net (code "71") (name "Net-(ETH2-RC)") (class "Default")
      (node (ref "ETH2") (pin "11") (pinfunction "RC_11") (pintype "passive"))
      (node (ref "R11") (pin "2") (pinfunction "2_2") (pintype "passive"))
    )
    (net (code "72") (name "Net-(ETH3-LC)") (class "Default")
      (node (ref "ETH3") (pin "10") (pinfunction "LC_10") (pintype "passive"))
      (node (ref "R6") (pin "2") (pinfunction "2_2") (pintype "passive"))
    )
    (net (code "73") (name "Net-(ETH3-RC)") (class "Default")
      (node (ref "ETH3") (pin "11") (pinfunction "RC_11") (pintype "passive"))
      (node (ref "R7") (pin "2") (pinfunction "2_2") (pintype "passive"))
    )
    (net (code "74") (name "Net-(ETH4-LC)") (class "Default")
      (node (ref "ETH4") (pin "10") (pinfunction "LC_10") (pintype "passive"))
      (node (ref "R60") (pin "2") (pinfunction "2_2") (pintype "passive"))
    )
    (net (code "75") (name "Net-(ETH4-RC)") (class "Default")
      (node (ref "ETH4") (pin "11") (pinfunction "RC_11") (pintype "passive"))
      (node (ref "R61") (pin "2") (pinfunction "2_2") (pintype "passive"))
    )
    (net (code "76") (name "Net-(ETH5-LC)") (class "Default")
      (node (ref "ETH5") (pin "10") (pinfunction "LC_10") (pintype "passive"))
      (node (ref "R8") (pin "2") (pinfunction "2_2") (pintype "passive"))
    )
    (net (code "77") (name "Net-(ETH5-RC)") (class "Default")
      (node (ref "ETH5") (pin "11") (pinfunction "RC_11") (pintype "passive"))
      (node (ref "R9") (pin "2") (pinfunction "2_2") (pintype "passive"))
    )
    (net (code "78") (name "Net-(IC1-ISET)") (class "Default")
      (node (ref "IC1") (pin "17") (pinfunction "ISET_17") (pintype "bidirectional"))
      (node (ref "R1") (pin "2") (pinfunction "2_2") (pintype "passive"))
    )
    (net (code "79") (name "Net-(IC1-X1)") (class "Default")
      (node (ref "C3") (pin "1") (pinfunction "1_1") (pintype "passive"))
      (node (ref "IC1") (pin "121") (pinfunction "X1_121") (pintype "bidirectional"))
      (node (ref "Y2") (pin "3") (pinfunction "2_3") (pintype "passive"))
    )
    (net (code "80") (name "Net-(IC1-X2)") (class "Default")
      (node (ref "C2") (pin "1") (pinfunction "1_1") (pintype "passive"))
      (node (ref "IC1") (pin "122") (pinfunction "X2_122") (pintype "bidirectional"))
      (node (ref "Y2") (pin "1") (pinfunction "1_1") (pintype "passive"))
    )
    (net (code "81") (name "Net-(IC3-ADJ)") (class "Default")
      (node (ref "IC3") (pin "1") (pinfunction "ADJ_1") (pintype "input"))
      (node (ref "R26") (pin "1") (pinfunction "1_1") (pintype "passive"))
      (node (ref "R27") (pin "2") (pinfunction "2_2") (pintype "passive"))
    )
    (net (code "82") (name "Net-(IC4-ADJ)") (class "Default")
      (node (ref "IC4") (pin "1") (pinfunction "ADJ_1") (pintype "input"))
      (node (ref "R24") (pin "1") (pinfunction "1_1") (pintype "passive"))
      (node (ref "R25") (pin "2") (pinfunction "2_2") (pintype "passive"))
    )
    (net (code "83") (name "Net-(LED1-PadC)") (class "Default")
      (node (ref "LED1") (pin "C") (pinfunction "C_C") (pintype "passive"))
      (node (ref "R14") (pin "2") (pinfunction "2_2") (pintype "passive"))
    )
    (net (code "84") (name "Net-(LED3-PadC)") (class "Default")
      (node (ref "LED3") (pin "C") (pinfunction "C_C") (pintype "passive"))
      (node (ref "R23") (pin "2") (pinfunction "2_2") (pintype "passive"))
    )
    (net (code "85") (name "Net-(R15-Pad2)") (class "Default")
      (node (ref "R15") (pin "2") (pinfunction "2_2") (pintype "passive"))
      (node (ref "R17") (pin "1") (pinfunction "1_1") (pintype "passive"))
      (node (ref "U$1") (pin "D-") (pinfunction "D-_D-") (pintype "bidirectional"))
    )
    (net (code "86") (name "Net-(R16-Pad2)") (class "Default")
      (node (ref "R16") (pin "2") (pinfunction "2_2") (pintype "passive"))
      (node (ref "U$1") (pin "D+") (pinfunction "D+_D+") (pintype "bidirectional"))
    )
    (net (code "87") (name "unconnected-(ETH1-NC-Pad7)") (class "Default")
      (node (ref "ETH1") (pin "7") (pinfunction "NC_7") (pintype "passive"))
    )
    (net (code "88") (name "unconnected-(ETH2-NC-Pad7)") (class "Default")
      (node (ref "ETH2") (pin "7") (pinfunction "NC_7") (pintype "passive"))
    )
    (net (code "89") (name "unconnected-(ETH3-NC-Pad7)") (class "Default")
      (node (ref "ETH3") (pin "7") (pinfunction "NC_7") (pintype "passive"))
    )
    (net (code "90") (name "unconnected-(ETH4-NC-Pad7)") (class "Default")
      (node (ref "ETH4") (pin "7") (pinfunction "NC_7") (pintype "passive"))
    )
    (net (code "91") (name "unconnected-(ETH5-NC-Pad7)") (class "Default")
      (node (ref "ETH5") (pin "7") (pinfunction "NC_7") (pintype "passive"))
    )
    (net (code "92") (name "unconnected-(IC1-FXSD4-Pad39)") (class "Default")
      (node (ref "IC1") (pin "39") (pinfunction "FXSD4_39") (pintype "bidirectional"))
    )
    (net (code "93") (name "unconnected-(IC1-FXSD5-Pad38)") (class "Default")
      (node (ref "IC1") (pin "38") (pinfunction "FXSD5_38") (pintype "bidirectional"))
    )
    (net (code "94") (name "unconnected-(IC1-MDC-Pad107)") (class "Default")
      (node (ref "IC1") (pin "107") (pinfunction "MDC_107") (pintype "bidirectional"))
    )
    (net (code "95") (name "unconnected-(IC1-MDI-XDIS-Pad1)") (class "Default")
      (node (ref "IC1") (pin "1") (pinfunction "MDI-XDIS_1") (pintype "bidirectional"))
    )
    (net (code "96") (name "unconnected-(IC1-MDIO-Pad108)") (class "Default")
      (node (ref "IC1") (pin "108") (pinfunction "MDIO_108") (pintype "bidirectional"))
    )
    (net (code "97") (name "unconnected-(IC1-MUX1-Pad45)") (class "Default")
      (node (ref "IC1") (pin "45") (pinfunction "MUX1_45") (pintype "bidirectional"))
    )
    (net (code "98") (name "unconnected-(IC1-MUX2-Pad46)") (class "Default")
      (node (ref "IC1") (pin "46") (pinfunction "MUX2_46") (pintype "bidirectional"))
    )
    (net (code "99") (name "unconnected-(IC1-NC-Pad120)") (class "Default")
      (node (ref "IC1") (pin "120") (pinfunction "NC_120") (pintype "bidirectional"))
    )
    (net (code "100") (name "unconnected-(IC1-PCOL-Pad68)") (class "Default")
      (node (ref "IC1") (pin "68") (pinfunction "PCOL_68") (pintype "bidirectional"))
    )
    (net (code "101") (name "unconnected-(IC1-PCRS-Pad67)") (class "Default")
      (node (ref "IC1") (pin "67") (pinfunction "PCRS_67") (pintype "bidirectional"))
    )
    (net (code "102") (name "unconnected-(IC1-PMRXC-Pad60)") (class "Default")
      (node (ref "IC1") (pin "60") (pinfunction "PMRXC_60") (pintype "bidirectional"))
    )
    (net (code "103") (name "unconnected-(IC1-PMRXD0-Pad65)") (class "Default")
      (node (ref "IC1") (pin "65") (pinfunction "PMRXD0_65") (pintype "bidirectional"))
    )
    (net (code "104") (name "unconnected-(IC1-PMRXD1-Pad64)") (class "Default")
      (node (ref "IC1") (pin "64") (pinfunction "PMRXD1_64") (pintype "bidirectional"))
    )
    (net (code "105") (name "unconnected-(IC1-PMRXD2-Pad63)") (class "Default")
      (node (ref "IC1") (pin "63") (pinfunction "PMRXD2_63") (pintype "bidirectional"))
    )
    (net (code "106") (name "unconnected-(IC1-PMRXD3-Pad62)") (class "Default")
      (node (ref "IC1") (pin "62") (pinfunction "PMRXD3_62") (pintype "bidirectional"))
    )
    (net (code "107") (name "unconnected-(IC1-PMRXDV-Pad61)") (class "Default")
      (node (ref "IC1") (pin "61") (pinfunction "PMRXDV_61") (pintype "bidirectional"))
    )
    (net (code "108") (name "unconnected-(IC1-PMRXER-Pad66)") (class "Default")
      (node (ref "IC1") (pin "66") (pinfunction "PMRXER_66") (pintype "bidirectional"))
    )
    (net (code "109") (name "unconnected-(IC1-PMTXC-Pad57)") (class "Default")
      (node (ref "IC1") (pin "57") (pinfunction "PMTXC_57") (pintype "bidirectional"))
    )
    (net (code "110") (name "unconnected-(IC1-PMTXD0-Pad55)") (class "Default")
      (node (ref "IC1") (pin "55") (pinfunction "PMTXD0_55") (pintype "bidirectional"))
    )
    (net (code "111") (name "unconnected-(IC1-PMTXD1-Pad54)") (class "Default")
      (node (ref "IC1") (pin "54") (pinfunction "PMTXD1_54") (pintype "bidirectional"))
    )
    (net (code "112") (name "unconnected-(IC1-PMTXD2-Pad53)") (class "Default")
      (node (ref "IC1") (pin "53") (pinfunction "PMTXD2_53") (pintype "bidirectional"))
    )
    (net (code "113") (name "unconnected-(IC1-PMTXD3-Pad52)") (class "Default")
      (node (ref "IC1") (pin "52") (pinfunction "PMTXD3_52") (pintype "bidirectional"))
    )
    (net (code "114") (name "unconnected-(IC1-PMTXEN-Pad51)") (class "Default")
      (node (ref "IC1") (pin "51") (pinfunction "PMTXEN_51") (pintype "bidirectional"))
    )
    (net (code "115") (name "unconnected-(IC1-PMTXER-Pad56)") (class "Default")
      (node (ref "IC1") (pin "56") (pinfunction "PMTXER_56") (pintype "bidirectional"))
    )
    (net (code "116") (name "unconnected-(IC1-PWRDN_N-Pad47)") (class "Default")
      (node (ref "IC1") (pin "47") (pinfunction "PWRDN_N_47") (pintype "bidirectional"))
    )
    (net (code "117") (name "unconnected-(IC1-RESERVED-Pad48)") (class "Default")
      (node (ref "IC1") (pin "48") (pinfunction "RESERVED_48") (pintype "bidirectional"))
    )
    (net (code "118") (name "unconnected-(IC1-SCANEN-Pad119)") (class "Default")
      (node (ref "IC1") (pin "119") (pinfunction "SCANEN_119") (pintype "bidirectional"))
    )
    (net (code "119") (name "unconnected-(IC1-SCOL-Pad84)") (class "Default")
      (node (ref "IC1") (pin "84") (pinfunction "SCOL_84") (pintype "bidirectional"))
    )
    (net (code "120") (name "unconnected-(IC1-SCRS-Pad85)") (class "Default")
      (node (ref "IC1") (pin "85") (pinfunction "SCRS_85") (pintype "bidirectional"))
    )
    (net (code "121") (name "unconnected-(IC1-SMRXC-Pad78)") (class "Default")
      (node (ref "IC1") (pin "78") (pinfunction "SMRXC_78") (pintype "bidirectional"))
    )
    (net (code "122") (name "unconnected-(IC1-SMRXD0-Pad83)") (class "Default")
      (node (ref "IC1") (pin "83") (pinfunction "SMRXD0_83") (pintype "bidirectional"))
    )
    (net (code "123") (name "unconnected-(IC1-SMRXD1-Pad82)") (class "Default")
      (node (ref "IC1") (pin "82") (pinfunction "SMRXD1_82") (pintype "bidirectional"))
    )
    (net (code "124") (name "unconnected-(IC1-SMRXD2-Pad81)") (class "Default")
      (node (ref "IC1") (pin "81") (pinfunction "SMRXD2_81") (pintype "bidirectional"))
    )
    (net (code "125") (name "unconnected-(IC1-SMRXD3-Pad80)") (class "Default")
      (node (ref "IC1") (pin "80") (pinfunction "SMRXD3_80") (pintype "bidirectional"))
    )
    (net (code "126") (name "unconnected-(IC1-SMRXDV-Pad79)") (class "Default")
      (node (ref "IC1") (pin "79") (pinfunction "SMRXDV_79") (pintype "bidirectional"))
    )
    (net (code "127") (name "unconnected-(IC1-SMTXC-Pad75)") (class "Default")
      (node (ref "IC1") (pin "75") (pinfunction "SMTXC_75") (pintype "bidirectional"))
    )
    (net (code "128") (name "unconnected-(IC1-SMTXD0-Pad73)") (class "Default")
      (node (ref "IC1") (pin "73") (pinfunction "SMTXD0_73") (pintype "bidirectional"))
    )
    (net (code "129") (name "unconnected-(IC1-SMTXD1-Pad72)") (class "Default")
      (node (ref "IC1") (pin "72") (pinfunction "SMTXD1_72") (pintype "bidirectional"))
    )
    (net (code "130") (name "unconnected-(IC1-SMTXD2-Pad71)") (class "Default")
      (node (ref "IC1") (pin "71") (pinfunction "SMTXD2_71") (pintype "bidirectional"))
    )
    (net (code "131") (name "unconnected-(IC1-SMTXD3-Pad70)") (class "Default")
      (node (ref "IC1") (pin "70") (pinfunction "SMTXD3_70") (pintype "bidirectional"))
    )
    (net (code "132") (name "unconnected-(IC1-SMTXEN-Pad69)") (class "Default")
      (node (ref "IC1") (pin "69") (pinfunction "SMTXEN_69") (pintype "bidirectional"))
    )
    (net (code "133") (name "unconnected-(IC1-SMTXER-Pad74)") (class "Default")
      (node (ref "IC1") (pin "74") (pinfunction "SMTXER_74") (pintype "bidirectional"))
    )
    (net (code "134") (name "unconnected-(IC1-TEST2-Pad128)") (class "Default")
      (node (ref "IC1") (pin "128") (pinfunction "TEST2_128") (pintype "bidirectional"))
    )
    (net (code "135") (name "unconnected-(IC1-TESTEN-Pad118)") (class "Default")
      (node (ref "IC1") (pin "118") (pinfunction "TESTEN_118") (pintype "bidirectional"))
    )
    (net (code "136") (name "unconnected-(IC2-ADC6-Pad19)") (class "Default")
      (node (ref "IC2") (pin "19") (pinfunction "ADC6_19") (pintype "bidirectional"))
    )
    (net (code "137") (name "unconnected-(IC2-ADC7-Pad22)") (class "Default")
      (node (ref "IC2") (pin "22") (pinfunction "ADC7_22") (pintype "bidirectional"))
    )
    (net (code "138") (name "unconnected-(IC2-AREF-Pad20)") (class "Default")
      (node (ref "IC2") (pin "20") (pinfunction "AREF_20") (pintype "passive"))
    )
    (net (code "139") (name "unconnected-(IC2-PB0(ICP)-Pad12)") (class "Default")
      (node (ref "IC2") (pin "12") (pinfunction "PB0(ICP)_12") (pintype "bidirectional"))
    )
    (net (code "140") (name "unconnected-(IC2-PB1(OC1A)-Pad13)") (class "Default")
      (node (ref "IC2") (pin "13") (pinfunction "PB1(OC1A)_13") (pintype "bidirectional"))
    )
    (net (code "141") (name "unconnected-(IC2-PC0(ADC0)-Pad23)") (class "Default")
      (node (ref "IC2") (pin "23") (pinfunction "PC0(ADC0)_23") (pintype "bidirectional"))
    )
    (net (code "142") (name "unconnected-(IC2-PC2(ADC2)-Pad25)") (class "Default")
      (node (ref "IC2") (pin "25") (pinfunction "PC2(ADC2)_25") (pintype "bidirectional"))
    )
    (net (code "143") (name "unconnected-(IC2-PC3(ADC3)-Pad26)") (class "Default")
      (node (ref "IC2") (pin "26") (pinfunction "PC3(ADC3)_26") (pintype "bidirectional"))
    )
    (net (code "144") (name "unconnected-(IC2-PC4(ADC4{slash}SDA)-Pad27)") (class "Default")
      (node (ref "IC2") (pin "27") (pinfunction "PC4(ADC4/SDA)_27") (pintype "bidirectional"))
    )
    (net (code "145") (name "unconnected-(IC2-PC5(ADC5{slash}SCL)-Pad28)") (class "Default")
      (node (ref "IC2") (pin "28") (pinfunction "PC5(ADC5/SCL)_28") (pintype "bidirectional"))
    )
    (net (code "146") (name "unconnected-(IC2-PD0(RXD)-Pad30)") (class "Default")
      (node (ref "IC2") (pin "30") (pinfunction "PD0(RXD)_30") (pintype "bidirectional"))
    )
    (net (code "147") (name "unconnected-(IC2-PD5(T1)-Pad9)") (class "Default")
      (node (ref "IC2") (pin "9") (pinfunction "PD5(T1)_9") (pintype "bidirectional"))
    )
    (net (code "148") (name "unconnected-(IC2-PD6(AIN0)-Pad10)") (class "Default")
      (node (ref "IC2") (pin "10") (pinfunction "PD6(AIN0)_10") (pintype "bidirectional"))
    )
    (net (code "149") (name "unconnected-(IC2-PD7(AIN1)-Pad11)") (class "Default")
      (node (ref "IC2") (pin "11") (pinfunction "PD7(AIN1)_11") (pintype "bidirectional"))
    )
    (net (code "150") (name "unconnected-(U$1-PadID)") (class "Default")
      (node (ref "U$1") (pin "ID") (pinfunction "ID_ID") (pintype "bidirectional"))
    )
  )
)
